# FEEDERLINK12.net
KiCad netlist of a schematic drawn in EAGLE
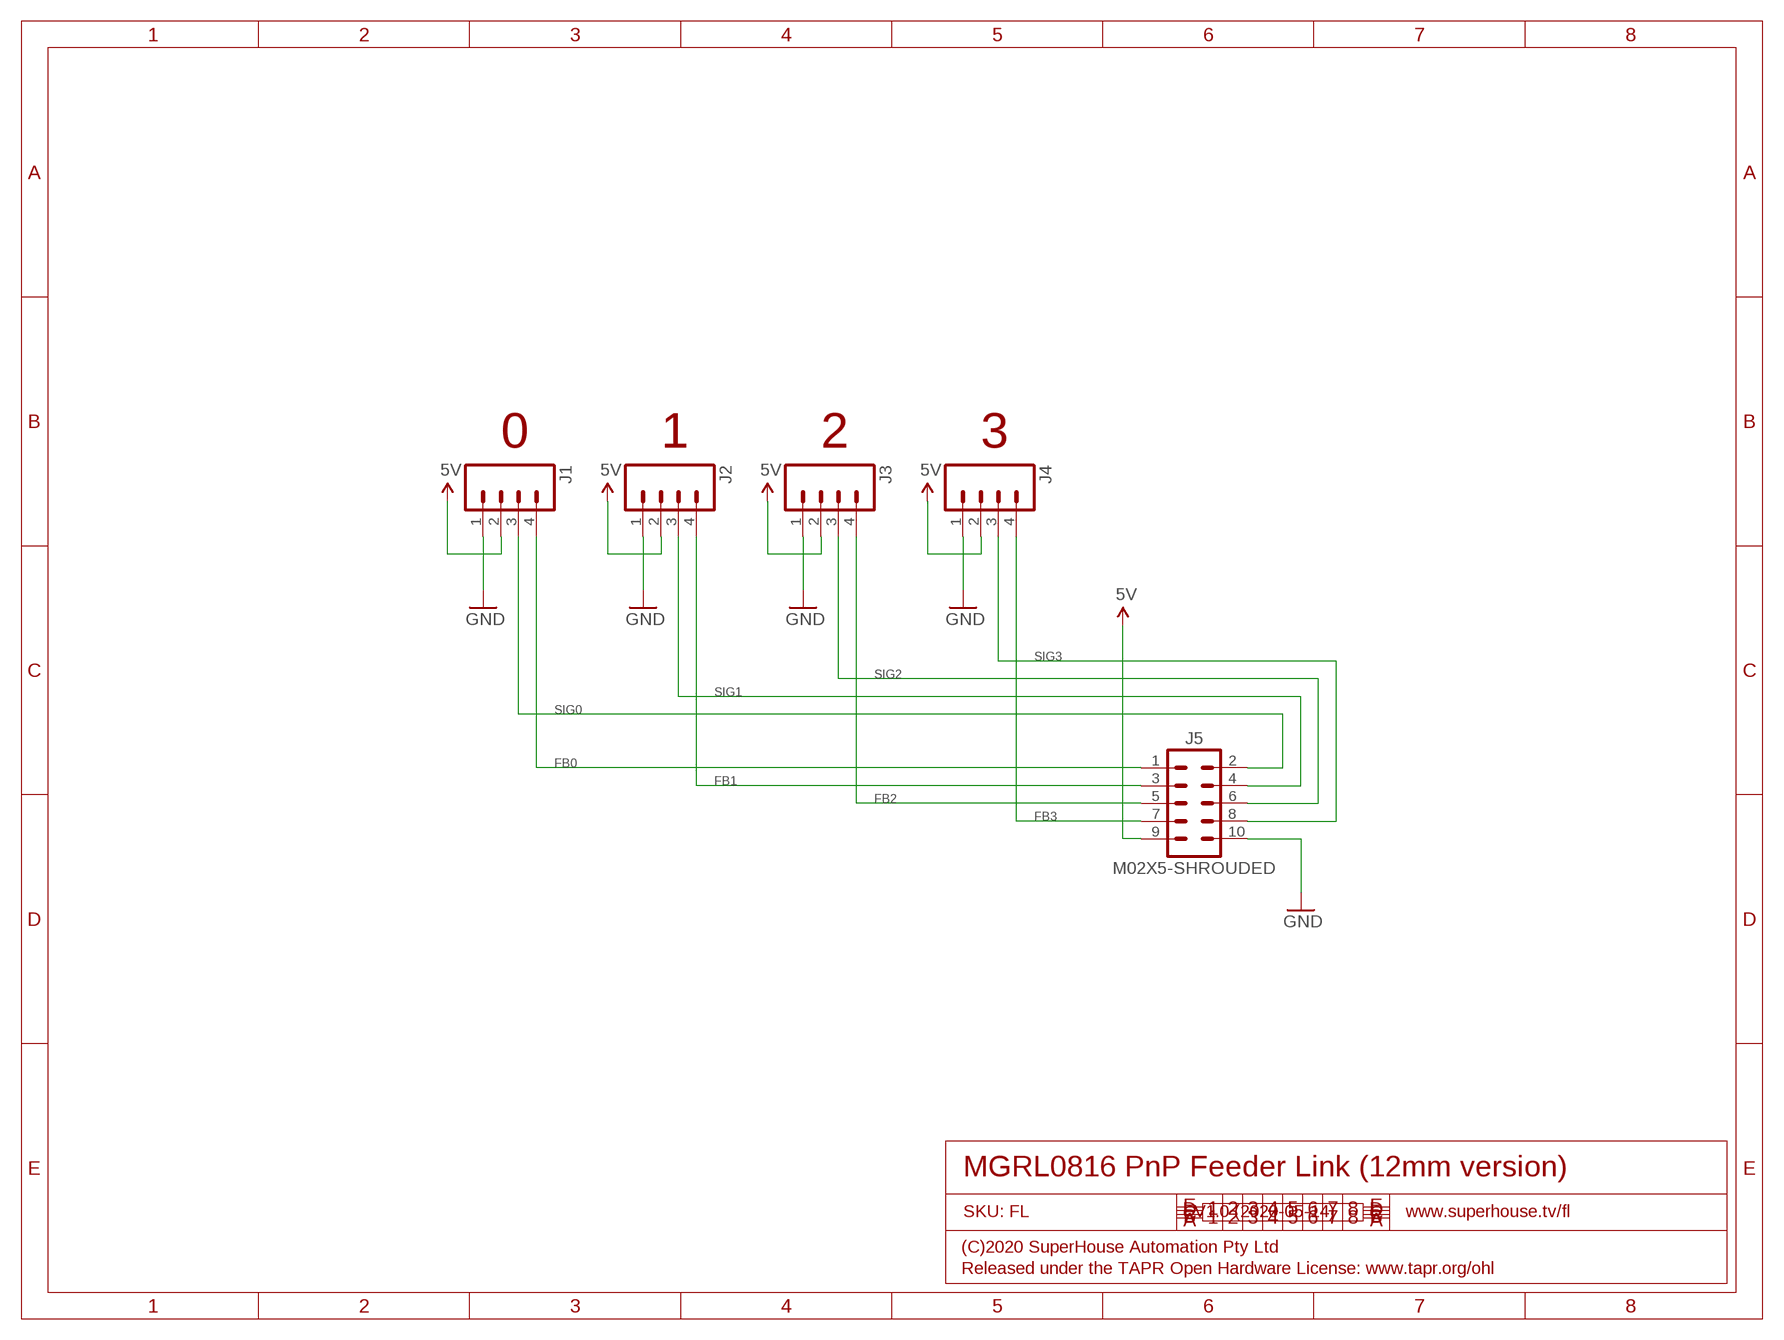
[diagram p0: schematic, sheet 1]

(export (version "E")
  (design (tool "Eeschema 10.0.6"))
  (components
    (comp (ref "J1")
      (value "M04-SOCKET")
      (footprint "eagle-import:1X04-S")
      (libsource (lib "eagle-import") (part "M04-SOCKET"))
    )
    (comp (ref "J2")
      (value "M04-SOCKET")
      (footprint "eagle-import:1X04-S")
      (libsource (lib "eagle-import") (part "M04-SOCKET"))
    )
    (comp (ref "J3")
      (value "M04-SOCKET")
      (footprint "eagle-import:1X04-S")
      (libsource (lib "eagle-import") (part "M04-SOCKET"))
    )
    (comp (ref "J4")
      (value "M04-SOCKET")
      (footprint "eagle-import:1X04-S")
      (libsource (lib "eagle-import") (part "M04-SOCKET"))
    )
    (comp (ref "J5")
      (value "M02X5-SHROUDED")
      (footprint "eagle-import:2X05-2.54-SHROUDED")
      (libsource (lib "eagle-import") (part "M02X5-SHROUDED"))
    )
  )
  (nets
    (net (code "1") (name "/FB0") (class "Default")
      (node (ref "J1") (pin "4") (pinfunction "4_4") (pintype "passive"))
      (node (ref "J5") (pin "1") (pinfunction "1_1") (pintype "passive"))
    )
    (net (code "2") (name "/FB1") (class "Default")
      (node (ref "J2") (pin "4") (pinfunction "4_4") (pintype "passive"))
      (node (ref "J5") (pin "3") (pinfunction "3_3") (pintype "passive"))
    )
    (net (code "3") (name "/FB2") (class "Default")
      (node (ref "J3") (pin "4") (pinfunction "4_4") (pintype "passive"))
      (node (ref "J5") (pin "5") (pinfunction "5_5") (pintype "passive"))
    )
    (net (code "4") (name "/FB3") (class "Default")
      (node (ref "J4") (pin "4") (pinfunction "4_4") (pintype "passive"))
      (node (ref "J5") (pin "7") (pinfunction "7_7") (pintype "passive"))
    )
    (net (code "5") (name "/SIG0") (class "Default")
      (node (ref "J1") (pin "3") (pinfunction "3_3") (pintype "passive"))
      (node (ref "J5") (pin "2") (pinfunction "2_2") (pintype "passive"))
    )
    (net (code "6") (name "/SIG1") (class "Default")
      (node (ref "J2") (pin "3") (pinfunction "3_3") (pintype "passive"))
      (node (ref "J5") (pin "4") (pinfunction "4_4") (pintype "passive"))
    )
    (net (code "7") (name "/SIG2") (class "Default")
      (node (ref "J3") (pin "3") (pinfunction "3_3") (pintype "passive"))
      (node (ref "J5") (pin "6") (pinfunction "6_6") (pintype "passive"))
    )
    (net (code "8") (name "/SIG3") (class "Default")
      (node (ref "J4") (pin "3") (pinfunction "3_3") (pintype "passive"))
      (node (ref "J5") (pin "8") (pinfunction "8_8") (pintype "passive"))
    )
    (net (code "9") (name "5V") (class "Default")
      (node (ref "J1") (pin "2") (pinfunction "2_2") (pintype "passive"))
      (node (ref "J2") (pin "2") (pinfunction "2_2") (pintype "passive"))
      (node (ref "J3") (pin "2") (pinfunction "2_2") (pintype "passive"))
      (node (ref "J4") (pin "2") (pinfunction "2_2") (pintype "passive"))
      (node (ref "J5") (pin "9") (pinfunction "9_9") (pintype "passive"))
    )
    (net (code "10") (name "GND") (class "Default")
      (node (ref "J1") (pin "1") (pinfunction "1_1") (pintype "passive"))
      (node (ref "J2") (pin "1") (pinfunction "1_1") (pintype "passive"))
      (node (ref "J3") (pin "1") (pinfunction "1_1") (pintype "passive"))
      (node (ref "J4") (pin "1") (pinfunction "1_1") (pintype "passive"))
      (node (ref "J5") (pin "10") (pinfunction "10_10") (pintype "passive"))
    )
  )
)
